# transc_MIWI434.net
KiCad netlist of a schematic drawn in Altium Designer
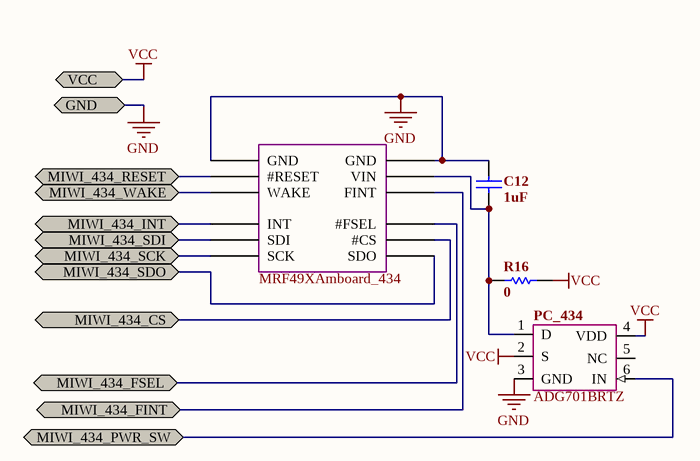
[diagram p0: transc_MIWI434.SchDoc]

(export (version "E")
  (design (tool "Eeschema 10.0.6"))
  (components
    (comp (ref "C12")
      (value "1uF")
      (footprint "1608[0603]")
      (description "Capacitor")
      (fields (field (name "Comment") "Cap"))
      (libsource (lib "Miscellaneous Devices") (part "Cap"))
    )
    (comp (ref "MRF49XAmboard_434")
      (value "MRF49XAmboard")
      (footprint "MRF49XAmboard")
      (description "Microchip RF radio")
      (libsource (lib "agus_lib") (part "MRF49XAmboard"))
    )
    (comp (ref "PC_434")
      (value "ADG701BRTZ")
      (footprint "SOT23-6_L")
      (libsource (lib "PlacaBase_agus") (part "ADG701BRTZ"))
    )
    (comp (ref "R16")
      (value "0")
      (footprint "1608[0603]")
      (description "Resistor")
      (fields (field (name "Comment") "resistor"))
      (libsource (lib "agus_lib") (part "RES"))
    )
  )
  (nets
    (net (code "1") (name "/MIWI_434_CS") (class "Default")
      (node (ref "MRF49XAmboard_434") (pin "8") (pinfunction "#CS_8") (pintype "passive"))
    )
    (net (code "2") (name "/MIWI_434_FINT") (class "Default")
      (node (ref "MRF49XAmboard_434") (pin "10") (pinfunction "FINT_10") (pintype "passive"))
    )
    (net (code "3") (name "/MIWI_434_FSEL") (class "Default")
      (node (ref "MRF49XAmboard_434") (pin "9") (pinfunction "#FSEL_9") (pintype "passive"))
    )
    (net (code "4") (name "/MIWI_434_INT") (class "Default")
      (node (ref "MRF49XAmboard_434") (pin "4") (pinfunction "INT_4") (pintype "passive"))
    )
    (net (code "5") (name "/MIWI_434_PWR_SW") (class "Default")
      (node (ref "PC_434") (pin "6") (pinfunction "IN_6") (pintype "input"))
    )
    (net (code "6") (name "/MIWI_434_RESET") (class "Default")
      (node (ref "MRF49XAmboard_434") (pin "2") (pinfunction "#RESET_2") (pintype "passive"))
    )
    (net (code "7") (name "/MIWI_434_SCK") (class "Default")
      (node (ref "MRF49XAmboard_434") (pin "6") (pinfunction "SCK_6") (pintype "passive"))
    )
    (net (code "8") (name "/MIWI_434_SDI") (class "Default")
      (node (ref "MRF49XAmboard_434") (pin "5") (pinfunction "SDI_5") (pintype "passive"))
    )
    (net (code "9") (name "/MIWI_434_SDO") (class "Default")
      (node (ref "MRF49XAmboard_434") (pin "7") (pinfunction "SDO_7") (pintype "passive"))
    )
    (net (code "10") (name "/MIWI_434_WAKE") (class "Default")
      (node (ref "MRF49XAmboard_434") (pin "3") (pinfunction "WAKE_3") (pintype "passive"))
    )
    (net (code "11") (name "GND") (class "Default")
      (node (ref "C12") (pin "1") (pinfunction "1_1") (pintype "passive"))
      (node (ref "MRF49XAmboard_434") (pin "1") (pinfunction "GND_1") (pintype "passive"))
      (node (ref "MRF49XAmboard_434") (pin "12") (pinfunction "GND_12") (pintype "passive"))
      (node (ref "PC_434") (pin "3") (pinfunction "GND_3") (pintype "passive"))
    )
    (net (code "12") (name "Net-(MRF49XAmboard_434-VIN)") (class "Default")
      (node (ref "C12") (pin "2") (pinfunction "2_2") (pintype "passive"))
      (node (ref "MRF49XAmboard_434") (pin "11") (pinfunction "VIN_11") (pintype "passive"))
      (node (ref "PC_434") (pin "1") (pinfunction "D_1") (pintype "bidirectional"))
      (node (ref "R16") (pin "2") (pinfunction "2_2") (pintype "passive"))
    )
    (net (code "13") (name "VCC") (class "Default")
      (node (ref "PC_434") (pin "2") (pinfunction "S_2") (pintype "bidirectional"))
      (node (ref "PC_434") (pin "4") (pinfunction "VDD_4") (pintype "power_in"))
      (node (ref "R16") (pin "1") (pinfunction "1_1") (pintype "passive"))
    )
    (net (code "14") (name "unconnected-(PC_434-NC-Pad5)") (class "Default")
      (node (ref "PC_434") (pin "5") (pinfunction "NC_5") (pintype "passive"))
    )
  )
)
